# 2_cyber60-mx_matrix.net
KiCad netlist of a schematic drawn in Altium Designer
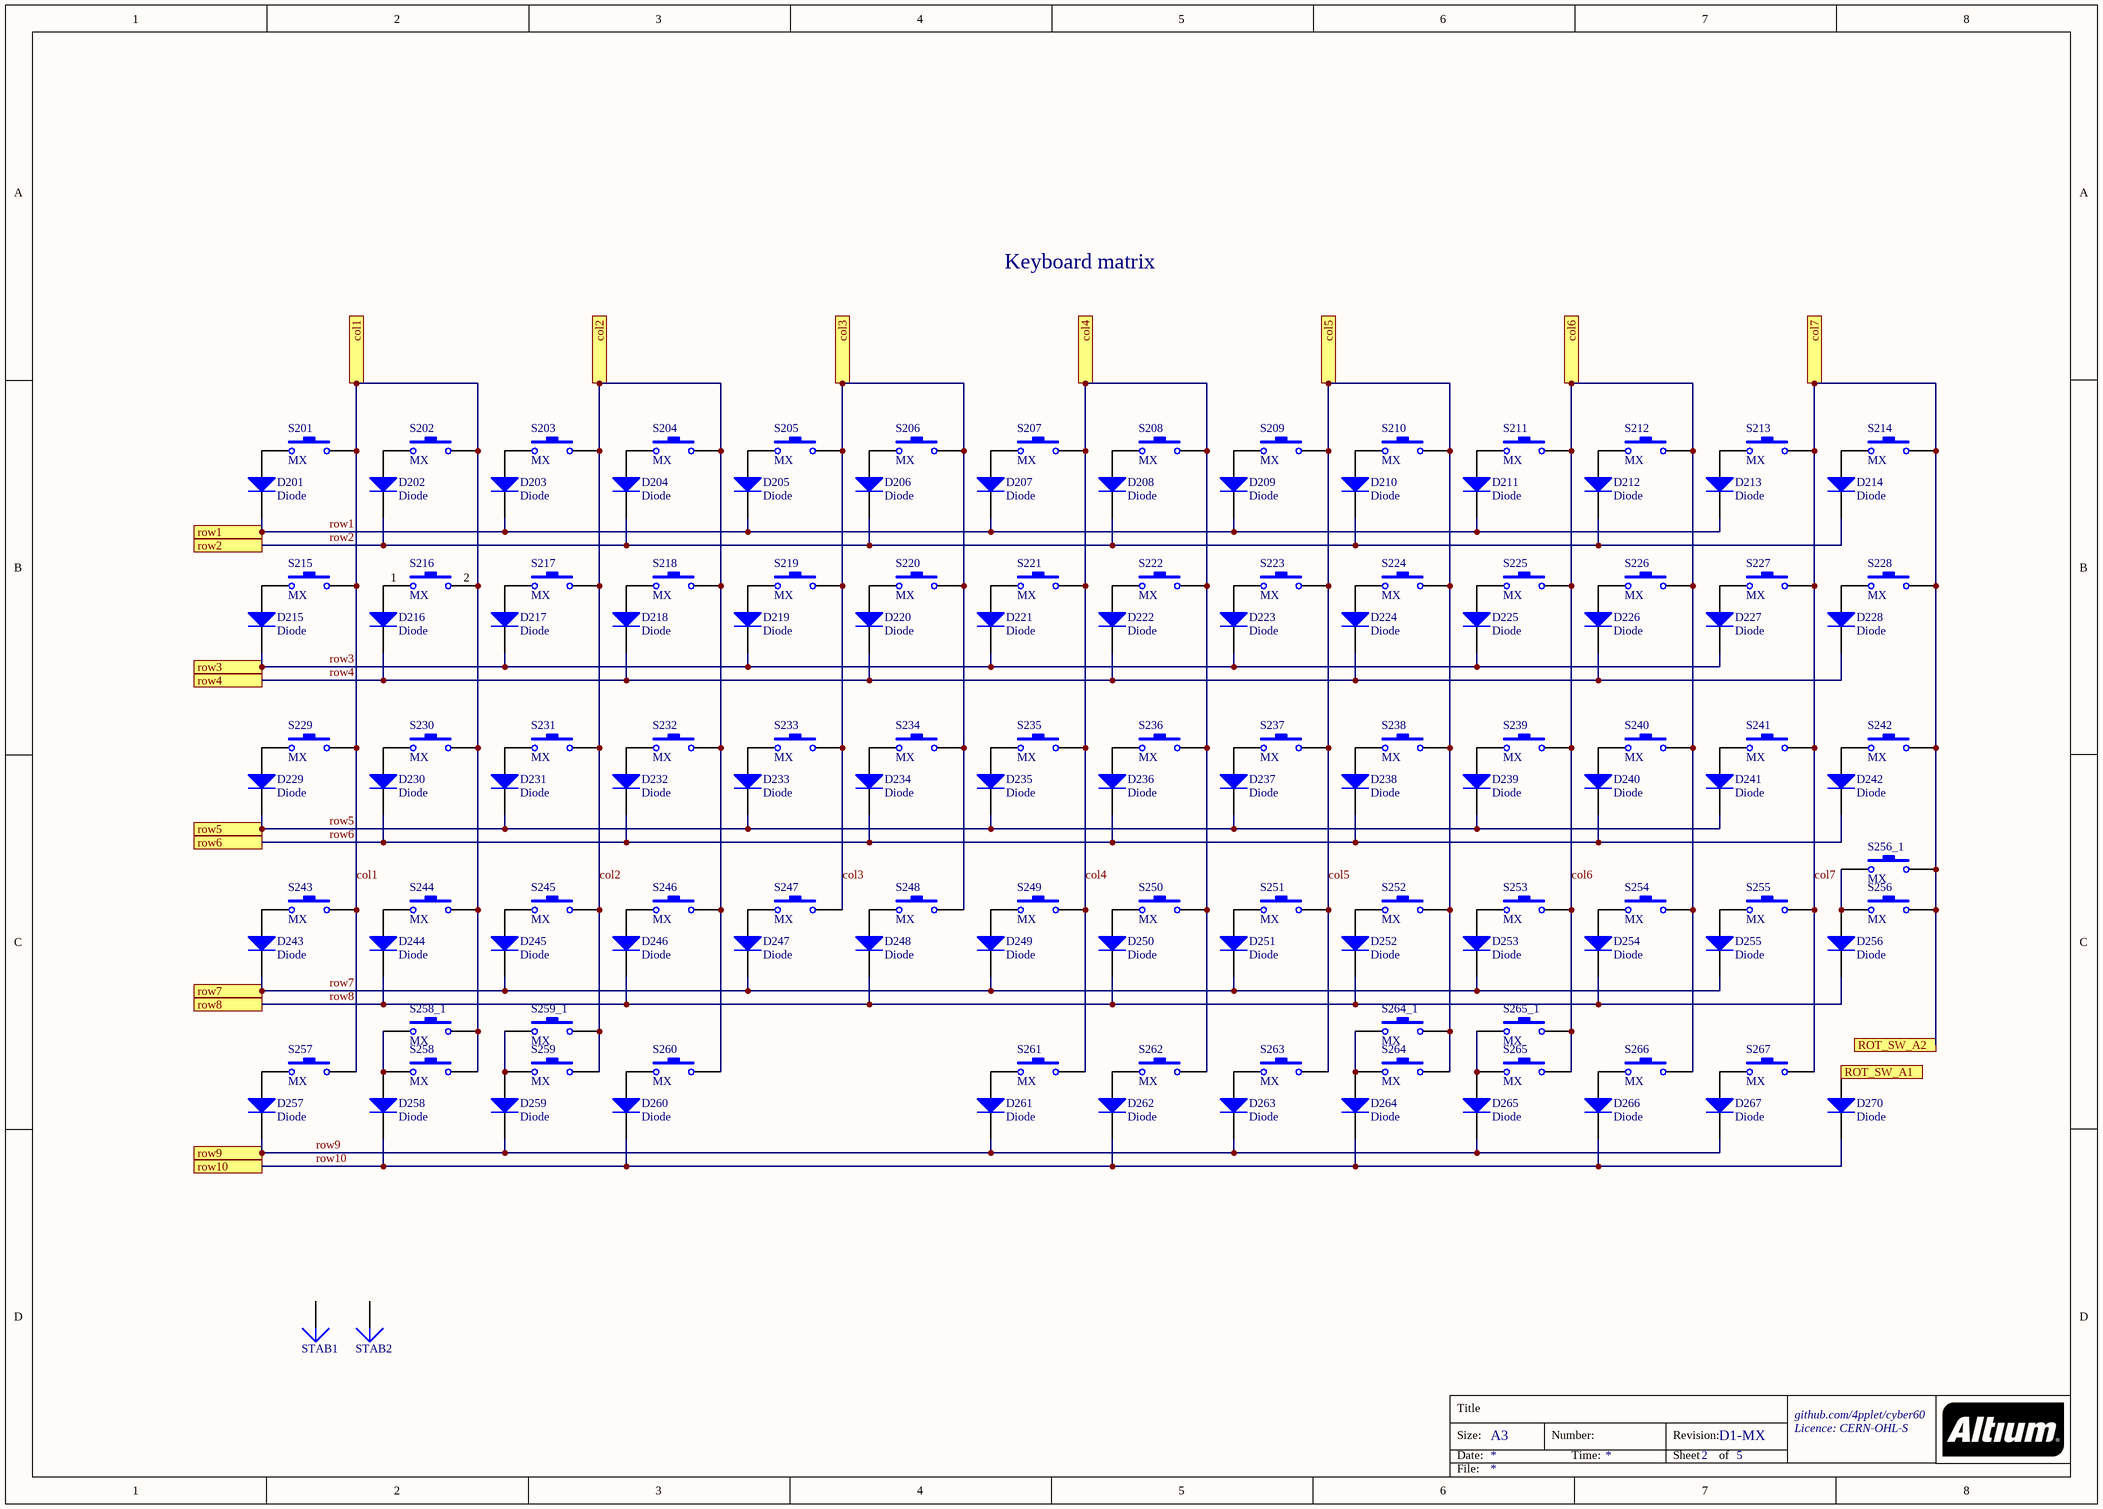
[diagram p0: 2_cyber60-mx_matrix.SchDoc]

(export (version "E")
  (design (tool "Eeschema 10.0.6"))
  (components
    (comp (ref "D201")
      (value "Diode")
      (footprint "SOD-123")
      (description "Default Diode")
      (fields (field (name "LCSC PART #") "C81598") (field (name "MRF.PART") "1N4148W"))
      (libsource (lib "Miscellaneous Devices") (part "Diode"))
    )
    (comp (ref "D202")
      (value "Diode")
      (footprint "SOD-123")
      (description "Default Diode")
      (fields (field (name "LCSC PART #") "C81598") (field (name "MRF.PART") "1N4148W"))
      (libsource (lib "Miscellaneous Devices") (part "Diode"))
    )
    (comp (ref "D203")
      (value "Diode")
      (footprint "SOD-123")
      (description "Default Diode")
      (fields (field (name "LCSC PART #") "C81598") (field (name "MRF.PART") "1N4148W"))
      (libsource (lib "Miscellaneous Devices") (part "Diode"))
    )
    (comp (ref "D204")
      (value "Diode")
      (footprint "SOD-123")
      (description "Default Diode")
      (fields (field (name "LCSC PART #") "C81598") (field (name "MRF.PART") "1N4148W"))
      (libsource (lib "Miscellaneous Devices") (part "Diode"))
    )
    (comp (ref "D205")
      (value "Diode")
      (footprint "SOD-123")
      (description "Default Diode")
      (fields (field (name "LCSC PART #") "C81598") (field (name "MRF.PART") "1N4148W"))
      (libsource (lib "Miscellaneous Devices") (part "Diode"))
    )
    (comp (ref "D206")
      (value "Diode")
      (footprint "SOD-123")
      (description "Default Diode")
      (fields (field (name "LCSC PART #") "C81598") (field (name "MRF.PART") "1N4148W"))
      (libsource (lib "Miscellaneous Devices") (part "Diode"))
    )
    (comp (ref "D207")
      (value "Diode")
      (footprint "SOD-123")
      (description "Default Diode")
      (fields (field (name "LCSC PART #") "C81598") (field (name "MRF.PART") "1N4148W"))
      (libsource (lib "Miscellaneous Devices") (part "Diode"))
    )
    (comp (ref "D208")
      (value "Diode")
      (footprint "SOD-123")
      (description "Default Diode")
      (fields (field (name "LCSC PART #") "C81598") (field (name "MRF.PART") "1N4148W"))
      (libsource (lib "Miscellaneous Devices") (part "Diode"))
    )
    (comp (ref "D209")
      (value "Diode")
      (footprint "SOD-123")
      (description "Default Diode")
      (fields (field (name "LCSC PART #") "C81598") (field (name "MRF.PART") "1N4148W"))
      (libsource (lib "Miscellaneous Devices") (part "Diode"))
    )
    (comp (ref "D210")
      (value "Diode")
      (footprint "SOD-123")
      (description "Default Diode")
      (fields (field (name "LCSC PART #") "C81598") (field (name "MRF.PART") "1N4148W"))
      (libsource (lib "Miscellaneous Devices") (part "Diode"))
    )
    (comp (ref "D211")
      (value "Diode")
      (footprint "SOD-123")
      (description "Default Diode")
      (fields (field (name "LCSC PART #") "C81598") (field (name "MRF.PART") "1N4148W"))
      (libsource (lib "Miscellaneous Devices") (part "Diode"))
    )
    (comp (ref "D212")
      (value "Diode")
      (footprint "SOD-123")
      (description "Default Diode")
      (fields (field (name "LCSC PART #") "C81598") (field (name "MRF.PART") "1N4148W"))
      (libsource (lib "Miscellaneous Devices") (part "Diode"))
    )
    (comp (ref "D213")
      (value "Diode")
      (footprint "SOD-123")
      (description "Default Diode")
      (fields (field (name "LCSC PART #") "C81598") (field (name "MRF.PART") "1N4148W"))
      (libsource (lib "Miscellaneous Devices") (part "Diode"))
    )
    (comp (ref "D214")
      (value "Diode")
      (footprint "SOD-123")
      (description "Default Diode")
      (fields (field (name "LCSC PART #") "C81598") (field (name "MRF.PART") "1N4148W"))
      (libsource (lib "Miscellaneous Devices") (part "Diode"))
    )
    (comp (ref "D215")
      (value "Diode")
      (footprint "SOD-123")
      (description "Default Diode")
      (fields (field (name "LCSC PART #") "C81598") (field (name "MRF.PART") "1N4148W"))
      (libsource (lib "Miscellaneous Devices") (part "Diode"))
    )
    (comp (ref "D216")
      (value "Diode")
      (footprint "SOD-123")
      (description "Default Diode")
      (fields (field (name "LCSC PART #") "C81598") (field (name "MRF.PART") "1N4148W"))
      (libsource (lib "Miscellaneous Devices") (part "Diode"))
    )
    (comp (ref "D217")
      (value "Diode")
      (footprint "SOD-123")
      (description "Default Diode")
      (fields (field (name "LCSC PART #") "C81598") (field (name "MRF.PART") "1N4148W"))
      (libsource (lib "Miscellaneous Devices") (part "Diode"))
    )
    (comp (ref "D218")
      (value "Diode")
      (footprint "SOD-123")
      (description "Default Diode")
      (fields (field (name "LCSC PART #") "C81598") (field (name "MRF.PART") "1N4148W"))
      (libsource (lib "Miscellaneous Devices") (part "Diode"))
    )
    (comp (ref "D219")
      (value "Diode")
      (footprint "SOD-123")
      (description "Default Diode")
      (fields (field (name "LCSC PART #") "C81598") (field (name "MRF.PART") "1N4148W"))
      (libsource (lib "Miscellaneous Devices") (part "Diode"))
    )
    (comp (ref "D220")
      (value "Diode")
      (footprint "SOD-123")
      (description "Default Diode")
      (fields (field (name "LCSC PART #") "C81598") (field (name "MRF.PART") "1N4148W"))
      (libsource (lib "Miscellaneous Devices") (part "Diode"))
    )
    (comp (ref "D221")
      (value "Diode")
      (footprint "SOD-123")
      (description "Default Diode")
      (fields (field (name "LCSC PART #") "C81598") (field (name "MRF.PART") "1N4148W"))
      (libsource (lib "Miscellaneous Devices") (part "Diode"))
    )
    (comp (ref "D222")
      (value "Diode")
      (footprint "SOD-123")
      (description "Default Diode")
      (fields (field (name "LCSC PART #") "C81598") (field (name "MRF.PART") "1N4148W"))
      (libsource (lib "Miscellaneous Devices") (part "Diode"))
    )
    (comp (ref "D223")
      (value "Diode")
      (footprint "SOD-123")
      (description "Default Diode")
      (fields (field (name "LCSC PART #") "C81598") (field (name "MRF.PART") "1N4148W"))
      (libsource (lib "Miscellaneous Devices") (part "Diode"))
    )
    (comp (ref "D224")
      (value "Diode")
      (footprint "SOD-123")
      (description "Default Diode")
      (fields (field (name "LCSC PART #") "C81598") (field (name "MRF.PART") "1N4148W"))
      (libsource (lib "Miscellaneous Devices") (part "Diode"))
    )
    (comp (ref "D225")
      (value "Diode")
      (footprint "SOD-123")
      (description "Default Diode")
      (fields (field (name "LCSC PART #") "C81598") (field (name "MRF.PART") "1N4148W"))
      (libsource (lib "Miscellaneous Devices") (part "Diode"))
    )
    (comp (ref "D226")
      (value "Diode")
      (footprint "SOD-123")
      (description "Default Diode")
      (fields (field (name "LCSC PART #") "C81598") (field (name "MRF.PART") "1N4148W"))
      (libsource (lib "Miscellaneous Devices") (part "Diode"))
    )
    (comp (ref "D227")
      (value "Diode")
      (footprint "SOD-123")
      (description "Default Diode")
      (fields (field (name "LCSC PART #") "C81598") (field (name "MRF.PART") "1N4148W"))
      (libsource (lib "Miscellaneous Devices") (part "Diode"))
    )
    (comp (ref "D228")
      (value "Diode")
      (footprint "SOD-123")
      (description "Default Diode")
      (fields (field (name "LCSC PART #") "C81598") (field (name "MRF.PART") "1N4148W"))
      (libsource (lib "Miscellaneous Devices") (part "Diode"))
    )
    (comp (ref "D229")
      (value "Diode")
      (footprint "SOD-123")
      (description "Default Diode")
      (fields (field (name "LCSC PART #") "C81598") (field (name "MRF.PART") "1N4148W"))
      (libsource (lib "Miscellaneous Devices") (part "Diode"))
    )
    (comp (ref "D230")
      (value "Diode")
      (footprint "SOD-123")
      (description "Default Diode")
      (fields (field (name "LCSC PART #") "C81598") (field (name "MRF.PART") "1N4148W"))
      (libsource (lib "Miscellaneous Devices") (part "Diode"))
    )
    (comp (ref "D231")
      (value "Diode")
      (footprint "SOD-123")
      (description "Default Diode")
      (fields (field (name "LCSC PART #") "C81598") (field (name "MRF.PART") "1N4148W"))
      (libsource (lib "Miscellaneous Devices") (part "Diode"))
    )
    (comp (ref "D232")
      (value "Diode")
      (footprint "SOD-123")
      (description "Default Diode")
      (fields (field (name "LCSC PART #") "C81598") (field (name "MRF.PART") "1N4148W"))
      (libsource (lib "Miscellaneous Devices") (part "Diode"))
    )
    (comp (ref "D233")
      (value "Diode")
      (footprint "SOD-123")
      (description "Default Diode")
      (fields (field (name "LCSC PART #") "C81598") (field (name "MRF.PART") "1N4148W"))
      (libsource (lib "Miscellaneous Devices") (part "Diode"))
    )
    (comp (ref "D234")
      (value "Diode")
      (footprint "SOD-123")
      (description "Default Diode")
      (fields (field (name "LCSC PART #") "C81598") (field (name "MRF.PART") "1N4148W"))
      (libsource (lib "Miscellaneous Devices") (part "Diode"))
    )
    (comp (ref "D235")
      (value "Diode")
      (footprint "SOD-123")
      (description "Default Diode")
      (fields (field (name "LCSC PART #") "C81598") (field (name "MRF.PART") "1N4148W"))
      (libsource (lib "Miscellaneous Devices") (part "Diode"))
    )
    (comp (ref "D236")
      (value "Diode")
      (footprint "SOD-123")
      (description "Default Diode")
      (fields (field (name "LCSC PART #") "C81598") (field (name "MRF.PART") "1N4148W"))
      (libsource (lib "Miscellaneous Devices") (part "Diode"))
    )
    (comp (ref "D237")
      (value "Diode")
      (footprint "SOD-123")
      (description "Default Diode")
      (fields (field (name "LCSC PART #") "C81598") (field (name "MRF.PART") "1N4148W"))
      (libsource (lib "Miscellaneous Devices") (part "Diode"))
    )
    (comp (ref "D238")
      (value "Diode")
      (footprint "SOD-123")
      (description "Default Diode")
      (fields (field (name "LCSC PART #") "C81598") (field (name "MRF.PART") "1N4148W"))
      (libsource (lib "Miscellaneous Devices") (part "Diode"))
    )
    (comp (ref "D239")
      (value "Diode")
      (footprint "SOD-123")
      (description "Default Diode")
      (fields (field (name "LCSC PART #") "C81598") (field (name "MRF.PART") "1N4148W"))
      (libsource (lib "Miscellaneous Devices") (part "Diode"))
    )
    (comp (ref "D240")
      (value "Diode")
      (footprint "SOD-123")
      (description "Default Diode")
      (fields (field (name "LCSC PART #") "C81598") (field (name "MRF.PART") "1N4148W"))
      (libsource (lib "Miscellaneous Devices") (part "Diode"))
    )
    (comp (ref "D241")
      (value "Diode")
      (footprint "SOD-123")
      (description "Default Diode")
      (fields (field (name "LCSC PART #") "C81598") (field (name "MRF.PART") "1N4148W"))
      (libsource (lib "Miscellaneous Devices") (part "Diode"))
    )
    (comp (ref "D242")
      (value "Diode")
      (footprint "SOD-123")
      (description "Default Diode")
      (fields (field (name "LCSC PART #") "C81598") (field (name "MRF.PART") "1N4148W"))
      (libsource (lib "Miscellaneous Devices") (part "Diode"))
    )
    (comp (ref "D243")
      (value "Diode")
      (footprint "SOD-123")
      (description "Default Diode")
      (fields (field (name "LCSC PART #") "C81598") (field (name "MRF.PART") "1N4148W"))
      (libsource (lib "Miscellaneous Devices") (part "Diode"))
    )
    (comp (ref "D244")
      (value "Diode")
      (footprint "SOD-123")
      (description "Default Diode")
      (fields (field (name "LCSC PART #") "C81598") (field (name "MRF.PART") "1N4148W"))
      (libsource (lib "Miscellaneous Devices") (part "Diode"))
    )
    (comp (ref "D245")
      (value "Diode")
      (footprint "SOD-123")
      (description "Default Diode")
      (fields (field (name "LCSC PART #") "C81598") (field (name "MRF.PART") "1N4148W"))
      (libsource (lib "Miscellaneous Devices") (part "Diode"))
    )
    (comp (ref "D246")
      (value "Diode")
      (footprint "SOD-123")
      (description "Default Diode")
      (fields (field (name "LCSC PART #") "C81598") (field (name "MRF.PART") "1N4148W"))
      (libsource (lib "Miscellaneous Devices") (part "Diode"))
    )
    (comp (ref "D247")
      (value "Diode")
      (footprint "SOD-123")
      (description "Default Diode")
      (fields (field (name "LCSC PART #") "C81598") (field (name "MRF.PART") "1N4148W"))
      (libsource (lib "Miscellaneous Devices") (part "Diode"))
    )
    (comp (ref "D248")
      (value "Diode")
      (footprint "SOD-123")
      (description "Default Diode")
      (fields (field (name "LCSC PART #") "C81598") (field (name "MRF.PART") "1N4148W"))
      (libsource (lib "Miscellaneous Devices") (part "Diode"))
    )
    (comp (ref "D249")
      (value "Diode")
      (footprint "SOD-123")
      (description "Default Diode")
      (fields (field (name "LCSC PART #") "C81598") (field (name "MRF.PART") "1N4148W"))
      (libsource (lib "Miscellaneous Devices") (part "Diode"))
    )
    (comp (ref "D250")
      (value "Diode")
      (footprint "SOD-123")
      (description "Default Diode")
      (fields (field (name "LCSC PART #") "C81598") (field (name "MRF.PART") "1N4148W"))
      (libsource (lib "Miscellaneous Devices") (part "Diode"))
    )
    (comp (ref "D251")
      (value "Diode")
      (footprint "SOD-123")
      (description "Default Diode")
      (fields (field (name "LCSC PART #") "C81598") (field (name "MRF.PART") "1N4148W"))
      (libsource (lib "Miscellaneous Devices") (part "Diode"))
    )
    (comp (ref "D252")
      (value "Diode")
      (footprint "SOD-123")
      (description "Default Diode")
      (fields (field (name "LCSC PART #") "C81598") (field (name "MRF.PART") "1N4148W"))
      (libsource (lib "Miscellaneous Devices") (part "Diode"))
    )
    (comp (ref "D253")
      (value "Diode")
      (footprint "SOD-123")
      (description "Default Diode")
      (fields (field (name "LCSC PART #") "C81598") (field (name "MRF.PART") "1N4148W"))
      (libsource (lib "Miscellaneous Devices") (part "Diode"))
    )
    (comp (ref "D254")
      (value "Diode")
      (footprint "SOD-123")
      (description "Default Diode")
      (fields (field (name "LCSC PART #") "C81598") (field (name "MRF.PART") "1N4148W"))
      (libsource (lib "Miscellaneous Devices") (part "Diode"))
    )
    (comp (ref "D255")
      (value "Diode")
      (footprint "SOD-123")
      (description "Default Diode")
      (fields (field (name "LCSC PART #") "C81598") (field (name "MRF.PART") "1N4148W"))
      (libsource (lib "Miscellaneous Devices") (part "Diode"))
    )
    (comp (ref "D256")
      (value "Diode")
      (footprint "SOD-123")
      (description "Default Diode")
      (fields (field (name "LCSC PART #") "C81598") (field (name "MRF.PART") "1N4148W"))
      (libsource (lib "Miscellaneous Devices") (part "Diode"))
    )
    (comp (ref "D257")
      (value "Diode")
      (footprint "SOD-123")
      (description "Default Diode")
      (fields (field (name "LCSC PART #") "C81598") (field (name "MRF.PART") "1N4148W"))
      (libsource (lib "Miscellaneous Devices") (part "Diode"))
    )
    (comp (ref "D258")
      (value "Diode")
      (footprint "SOD-123")
      (description "Default Diode")
      (fields (field (name "LCSC PART #") "C81598") (field (name "MRF.PART") "1N4148W"))
      (libsource (lib "Miscellaneous Devices") (part "Diode"))
    )
    (comp (ref "D259")
      (value "Diode")
      (footprint "SOD-123")
      (description "Default Diode")
      (fields (field (name "LCSC PART #") "C81598") (field (name "MRF.PART") "1N4148W"))
      (libsource (lib "Miscellaneous Devices") (part "Diode"))
    )
    (comp (ref "D260")
      (value "Diode")
      (footprint "SOD-123")
      (description "Default Diode")
      (fields (field (name "LCSC PART #") "C81598") (field (name "MRF.PART") "1N4148W"))
      (libsource (lib "Miscellaneous Devices") (part "Diode"))
    )
    (comp (ref "D261")
      (value "Diode")
      (footprint "SOD-123")
      (description "Default Diode")
      (fields (field (name "LCSC PART #") "C81598") (field (name "MRF.PART") "1N4148W"))
      (libsource (lib "Miscellaneous Devices") (part "Diode"))
    )
    (comp (ref "D262")
      (value "Diode")
      (footprint "SOD-123")
      (description "Default Diode")
      (fields (field (name "LCSC PART #") "C81598") (field (name "MRF.PART") "1N4148W"))
      (libsource (lib "Miscellaneous Devices") (part "Diode"))
    )
    (comp (ref "D263")
      (value "Diode")
      (footprint "SOD-123")
      (description "Default Diode")
      (fields (field (name "LCSC PART #") "C81598") (field (name "MRF.PART") "1N4148W"))
      (libsource (lib "Miscellaneous Devices") (part "Diode"))
    )
    (comp (ref "D264")
      (value "Diode")
      (footprint "SOD-123")
      (description "Default Diode")
      (fields (field (name "LCSC PART #") "C81598") (field (name "MRF.PART") "1N4148W"))
      (libsource (lib "Miscellaneous Devices") (part "Diode"))
    )
    (comp (ref "D265")
      (value "Diode")
      (footprint "SOD-123")
      (description "Default Diode")
      (fields (field (name "LCSC PART #") "C81598") (field (name "MRF.PART") "1N4148W"))
      (libsource (lib "Miscellaneous Devices") (part "Diode"))
    )
    (comp (ref "D266")
      (value "Diode")
      (footprint "SOD-123")
      (description "Default Diode")
      (fields (field (name "LCSC PART #") "C81598") (field (name "MRF.PART") "1N4148W"))
      (libsource (lib "Miscellaneous Devices") (part "Diode"))
    )
    (comp (ref "D267")
      (value "Diode")
      (footprint "SOD-123")
      (description "Default Diode")
      (fields (field (name "LCSC PART #") "C81598") (field (name "MRF.PART") "1N4148W"))
      (libsource (lib "Miscellaneous Devices") (part "Diode"))
    )
    (comp (ref "D270")
      (value "Diode")
      (footprint "SOD-123")
      (description "Default Diode")
      (fields (field (name "LCSC PART #") "C81598") (field (name "MRF.PART") "1N4148W"))
      (libsource (lib "Miscellaneous Devices") (part "Diode"))
    )
    (comp (ref "S201")
      (value "MX")
      (footprint "MX-switch - switched pol")
      (description "Switch")
      (libsource (lib "Miscellaneous Devices") (part "SW-PB"))
    )
    (comp (ref "S202")
      (value "MX")
      (footprint "MX-switch - switched pol - connector")
      (description "Switch")
      (libsource (lib "Miscellaneous Devices") (part "SW-PB"))
    )
    (comp (ref "S203")
      (value "MX")
      (footprint "MX-switch - switched pol")
      (description "Switch")
      (libsource (lib "Miscellaneous Devices") (part "SW-PB"))
    )
    (comp (ref "S204")
      (value "MX")
      (footprint "MX-switch")
      (description "Switch")
      (libsource (lib "Miscellaneous Devices") (part "SW-PB"))
    )
    (comp (ref "S205")
      (value "MX")
      (footprint "MX-switch - switched pol")
      (description "Switch")
      (libsource (lib "Miscellaneous Devices") (part "SW-PB"))
    )
    (comp (ref "S206")
      (value "MX")
      (footprint "MX-switch - switched pol")
      (description "Switch")
      (libsource (lib "Miscellaneous Devices") (part "SW-PB"))
    )
    (comp (ref "S207")
      (value "MX")
      (footprint "MX-switch - switched pol")
      (description "Switch")
      (libsource (lib "Miscellaneous Devices") (part "SW-PB"))
    )
    (comp (ref "S208")
      (value "MX")
      (footprint "MX-switch - switched pol")
      (description "Switch")
      (libsource (lib "Miscellaneous Devices") (part "SW-PB"))
    )
    (comp (ref "S209")
      (value "MX")
      (footprint "MX-switch - switched pol")
      (description "Switch")
      (libsource (lib "Miscellaneous Devices") (part "SW-PB"))
    )
    (comp (ref "S210")
      (value "MX")
      (footprint "MX-switch - switched pol")
      (description "Switch")
      (libsource (lib "Miscellaneous Devices") (part "SW-PB"))
    )
    (comp (ref "S211")
      (value "MX")
      (footprint "MX-switch - switched pol")
      (description "Switch")
      (libsource (lib "Miscellaneous Devices") (part "SW-PB"))
    )
    (comp (ref "S212")
      (value "MX")
      (footprint "MX-switch - switched pol")
      (description "Switch")
      (libsource (lib "Miscellaneous Devices") (part "SW-PB"))
    )
    (comp (ref "S213")
      (value "MX")
      (footprint "MX-switch - switched pol")
      (description "Switch")
      (libsource (lib "Miscellaneous Devices") (part "SW-PB"))
    )
    (comp (ref "S214")
      (value "MX")
      (footprint "MX-switch - switched pol")
      (description "Switch")
      (libsource (lib "Miscellaneous Devices") (part "SW-PB"))
    )
    (comp (ref "S215")
      (value "MX")
      (footprint "MX-switch - 1.5U - switched pol")
      (description "TAB")
      (libsource (lib "Miscellaneous Devices") (part "SW-PB"))
    )
    (comp (ref "S216")
      (value "MX")
      (footprint "MX-switch - switched pol")
      (description "Switch")
      (libsource (lib "") (part "SW-PB_1"))
    )
    (comp (ref "S217")
      (value "MX")
      (footprint "MX-switch - switched pol")
      (description "Switch")
      (libsource (lib "Miscellaneous Devices") (part "SW-PB"))
    )
    (comp (ref "S218")
      (value "MX")
      (footprint "MX-switch - switched pol")
      (description "Switch")
      (libsource (lib "Miscellaneous Devices") (part "SW-PB"))
    )
    (comp (ref "S219")
      (value "MX")
      (footprint "MX-switch - switched pol")
      (description "Switch")
      (libsource (lib "Miscellaneous Devices") (part "SW-PB"))
    )
    (comp (ref "S220")
      (value "MX")
      (footprint "MX-switch")
      (description "Switch")
      (libsource (lib "Miscellaneous Devices") (part "SW-PB"))
    )
    (comp (ref "S221")
      (value "MX")
      (footprint "MX-switch - switched pol")
      (description "Switch")
      (libsource (lib "Miscellaneous Devices") (part "SW-PB"))
    )
    (comp (ref "S222")
      (value "MX")
      (footprint "MX-switch - switched pol")
      (description "Switch")
      (libsource (lib "Miscellaneous Devices") (part "SW-PB"))
    )
    (comp (ref "S223")
      (value "MX")
      (footprint "MX-switch - switched pol")
      (description "Switch")
      (libsource (lib "Miscellaneous Devices") (part "SW-PB"))
    )
    (comp (ref "S224")
      (value "MX")
      (footprint "MX-switch - switched pol")
      (description "Switch")
      (libsource (lib "Miscellaneous Devices") (part "SW-PB"))
    )
    (comp (ref "S225")
      (value "MX")
      (footprint "MX-switch - switched pol")
      (description "Switch")
      (libsource (lib "Miscellaneous Devices") (part "SW-PB"))
    )
    (comp (ref "S226")
      (value "MX")
      (footprint "MX-switch")
      (description "Switch")
      (libsource (lib "Miscellaneous Devices") (part "SW-PB"))
    )
    (comp (ref "S227")
      (value "MX")
      (footprint "MX-switch")
      (description "Switch")
      (libsource (lib "Miscellaneous Devices") (part "SW-PB"))
    )
    (comp (ref "S228")
      (value "MX")
      (footprint "MX-switch - backspace")
      (description "Switch")
      (libsource (lib "Miscellaneous Devices") (part "SW-PB"))
    )
    (comp (ref "S229")
      (value "MX")
      (footprint "MX-switch - CAPS")
      (description "Switch")
      (libsource (lib "Miscellaneous Devices") (part "SW-PB"))
    )
    (comp (ref "S230")
      (value "MX")
      (footprint "MX-switch - switched pol")
      (description "Switch")
      (libsource (lib "Miscellaneous Devices") (part "SW-PB"))
    )
    (comp (ref "S231")
      (value "MX")
      (footprint "MX-switch - switched pol")
      (description "Switch")
      (libsource (lib "Miscellaneous Devices") (part "SW-PB"))
    )
    (comp (ref "S232")
      (value "MX")
      (footprint "MX-switch - switched pol")
      (description "Switch")
      (libsource (lib "Miscellaneous Devices") (part "SW-PB"))
    )
    (comp (ref "S233")
      (value "MX")
      (footprint "MX-switch - switched pol")
      (description "Switch")
      (libsource (lib "Miscellaneous Devices") (part "SW-PB"))
    )
    (comp (ref "S234")
      (value "MX")
      (footprint "MX-switch")
      (description "Switch")
      (libsource (lib "Miscellaneous Devices") (part "SW-PB"))
    )
    (comp (ref "S235")
      (value "MX")
      (footprint "MX-switch - switched pol")
      (description "Switch")
      (libsource (lib "Miscellaneous Devices") (part "SW-PB"))
    )
    (comp (ref "S236")
      (value "MX")
      (footprint "MX-switch - switched pol")
      (description "Switch")
      (libsource (lib "Miscellaneous Devices") (part "SW-PB"))
    )
    (comp (ref "S237")
      (value "MX")
      (footprint "MX-switch - switched pol")
      (description "Switch")
      (libsource (lib "Miscellaneous Devices") (part "SW-PB"))
    )
    (comp (ref "S238")
      (value "MX")
      (footprint "MX-switch - switched pol")
      (description "Switch")
      (libsource (lib "Miscellaneous Devices") (part "SW-PB"))
    )
    (comp (ref "S239")
      (value "MX")
      (footprint "MX-switch")
      (description "Switch")
      (libsource (lib "Miscellaneous Devices") (part "SW-PB"))
    )
    (comp (ref "S240")
      (value "MX")
      (footprint "MX-switch - switched pol")
      (description "Switch")
      (libsource (lib "Miscellaneous Devices") (part "SW-PB"))
    )
    (comp (ref "S241")
      (value "MX")
      (footprint "MX-switch")
      (description "Switch")
      (libsource (lib "Miscellaneous Devices") (part "SW-PB"))
    )
    (comp (ref "S242")
      (value "MX")
      (footprint "MX-switch - 1.5U")
      (description "Switch")
      (libsource (lib "Miscellaneous Devices") (part "SW-PB"))
    )
    (comp (ref "S243")
      (value "MX")
      (footprint "MX-switch - Left shift")
      (description "Switch")
      (libsource (lib "Miscellaneous Devices") (part "SW-PB"))
    )
    (comp (ref "S244")
      (value "MX")
      (footprint "MX-switch - switched pol")
      (description "Switch")
      (libsource (lib "Miscellaneous Devices") (part "SW-PB"))
    )
    (comp (ref "S245")
      (value "MX")
      (footprint "MX-switch - switched pol")
      (description "Switch")
      (libsource (lib "Miscellaneous Devices") (part "SW-PB"))
    )
    (comp (ref "S246")
      (value "MX")
      (footprint "MX-switch - switched pol")
      (description "Switch")
      (libsource (lib "Miscellaneous Devices") (part "SW-PB"))
    )
    (comp (ref "S247")
      (value "MX")
      (footprint "MX-switch - switched pol")
      (description "Switch")
      (libsource (lib "Miscellaneous Devices") (part "SW-PB"))
    )
    (comp (ref "S248")
      (value "MX")
      (footprint "MX-switch")
      (description "Switch")
      (libsource (lib "Miscellaneous Devices") (part "SW-PB"))
    )
    (comp (ref "S249")
      (value "MX")
      (footprint "MX-switch - switched pol")
      (description "Switch")
      (libsource (lib "Miscellaneous Devices") (part "SW-PB"))
    )
    (comp (ref "S250")
      (value "MX")
      (footprint "MX-switch")
      (description "Switch")
      (libsource (lib "Miscellaneous Devices") (part "SW-PB"))
    )
    (comp (ref "S251")
      (value "MX")
      (footprint "MX-switch - switched pol")
      (description "Switch")
      (libsource (lib "Miscellaneous Devices") (part "SW-PB"))
    )
    (comp (ref "S252")
      (value "MX")
      (footprint "MX-switch - switched pol")
      (description "Switch")
      (libsource (lib "Miscellaneous Devices") (part "SW-PB"))
    )
    (comp (ref "S253")
      (value "MX")
      (footprint "MX-switch - switched pol")
      (description "Switch")
      (libsource (lib "Miscellaneous Devices") (part "SW-PB"))
    )
    (comp (ref "S254")
      (value "MX")
      (footprint "MX-switch - switched pol")
      (description "Switch")
      (libsource (lib "Miscellaneous Devices") (part "SW-PB"))
    )
    (comp (ref "S255")
      (value "MX")
      (footprint "MX-switch")
      (description "Switch")
      (libsource (lib "Miscellaneous Devices") (part "SW-PB"))
    )
    (comp (ref "S256")
      (value "MX")
      (footprint "MX-switch - switched pol")
      (description "Switch")
      (libsource (lib "Miscellaneous Devices") (part "SW-PB"))
    )
    (comp (ref "S256_1")
      (value "MX")
      (footprint "MX-switch")
      (description "Switch")
      (libsource (lib "Miscellaneous Devices") (part "SW-PB"))
    )
    (comp (ref "S257")
      (value "MX")
      (footprint "MX-switch - 1.5u MOD-L")
      (description "Switch")
      (libsource (lib "Miscellaneous Devices") (part "SW-PB"))
    )
    (comp (ref "S258")
      (value "MX")
      (footprint "MX-switch - 1u MOD-L")
      (description "Switch")
      (libsource (lib "Miscellaneous Devices") (part "SW-PB"))
    )
    (comp (ref "S258_1")
      (value "MX")
      (footprint "MX-switch")
      (description "Switch")
      (libsource (lib "Miscellaneous Devices") (part "SW-PB"))
    )
    (comp (ref "S259")
      (value "MX")
      (footprint "MX-switch - 1.5u MOD-L")
      (description "Switch")
      (libsource (lib "Miscellaneous Devices") (part "SW-PB"))
    )
    (comp (ref "S259_1")
      (value "MX")
      (footprint "MX-switch - switched pol")
      (description "Switch")
      (libsource (lib "Miscellaneous Devices") (part "SW-PB"))
    )
    (comp (ref "S260")
      (value "MX")
      (footprint "MX-switch - 2.75U - rotated stab")
      (description "Switch")
      (libsource (lib "Miscellaneous Devices") (part "SW-PB"))
    )
    (comp (ref "S261")
      (value "MX")
      (footprint "MX-switch - Space_V2")
      (description "Switch")
      (libsource (lib "Miscellaneous Devices") (part "SW-PB"))
    )
    (comp (ref "S262")
      (value "MX")
      (footprint "MX-switch - 2.75U - rotated stab")
      (description "Switch")
      (libsource (lib "Miscellaneous Devices") (part "SW-PB"))
    )
    (comp (ref "S263")
      (value "MX")
      (footprint "MX-switch - switched pol")
      (description "Switch")
      (libsource (lib "Miscellaneous Devices") (part "SW-PB"))
    )
    (comp (ref "S264")
      (value "MX")
      (footprint "MX-switch - 1.5u MOD-R")
      (description "Switch")
      (libsource (lib "Miscellaneous Devices") (part "SW-PB"))
    )
    (comp (ref "S264_1")
      (value "MX")
      (footprint "MX-switch")
      (description "Switch")
      (libsource (lib "Miscellaneous Devices") (part "SW-PB"))
    )
    (comp (ref "S265")
      (value "MX")
      (footprint "MX-switch - 1u MOD-R")
      (description "Switch")
      (libsource (lib "Miscellaneous Devices") (part "SW-PB"))
    )
    (comp (ref "S265_1")
      (value "MX")
      (footprint "MX-switch")
      (description "Switch")
      (libsource (lib "Miscellaneous Devices") (part "SW-PB"))
    )
    (comp (ref "S266")
      (value "MX")
      (footprint "MX-switch - 1.5u MOD-R")
      (description "Switch")
      (libsource (lib "Miscellaneous Devices") (part "SW-PB"))
    )
    (comp (ref "S267")
      (value "MX")
      (footprint "MX-switch - right shift")
      (description "Switch")
      (libsource (lib "Miscellaneous Devices") (part "SW-PB"))
    )
    (comp (ref "STAB1")
      (value "Plug")
      (footprint "Stab 2u")
      (libsource (lib "Miscellaneous Connectors") (part "Plug"))
    )
    (comp (ref "STAB2")
      (value "Plug")
      (footprint "Stab 2u")
      (libsource (lib "Miscellaneous Connectors") (part "Plug"))
    )
  )
  (nets
    (net (code "1") (name "/ROT_SW_A1") (class "Default")
      (node (ref "D270") (pin "1") (pinfunction "A_1") (pintype "passive"))
    )
    (net (code "2") (name "/col1") (class "Default")
      (node (ref "S201") (pin "2") (pinfunction "2_2") (pintype "passive"))
      (node (ref "S202") (pin "2") (pinfunction "2_2") (pintype "passive"))
      (node (ref "S215") (pin "2") (pinfunction "2_2") (pintype "passive"))
      (node (ref "S216") (pin "2") (pinfunction "2_2") (pintype "passive"))
      (node (ref "S229") (pin "2") (pinfunction "2_2") (pintype "passive"))
      (node (ref "S230") (pin "2") (pinfunction "2_2") (pintype "passive"))
      (node (ref "S243") (pin "2") (pinfunction "2_2") (pintype "passive"))
      (node (ref "S244") (pin "2") (pinfunction "2_2") (pintype "passive"))
      (node (ref "S257") (pin "2") (pinfunction "2_2") (pintype "passive"))
      (node (ref "S258") (pin "2") (pinfunction "2_2") (pintype "passive"))
      (node (ref "S258_1") (pin "2") (pinfunction "2_2") (pintype "passive"))
    )
    (net (code "3") (name "/col2") (class "Default")
      (node (ref "S203") (pin "2") (pinfunction "2_2") (pintype "passive"))
      (node (ref "S204") (pin "2") (pinfunction "2_2") (pintype "passive"))
      (node (ref "S217") (pin "2") (pinfunction "2_2") (pintype "passive"))
      (node (ref "S218") (pin "2") (pinfunction "2_2") (pintype "passive"))
      (node (ref "S231") (pin "2") (pinfunction "2_2") (pintype "passive"))
      (node (ref "S232") (pin "2") (pinfunction "2_2") (pintype "passive"))
      (node (ref "S245") (pin "2") (pinfunction "2_2") (pintype "passive"))
      (node (ref "S246") (pin "2") (pinfunction "2_2") (pintype "passive"))
      (node (ref "S259") (pin "2") (pinfunction "2_2") (pintype "passive"))
      (node (ref "S259_1") (pin "2") (pinfunction "2_2") (pintype "passive"))
      (node (ref "S260") (pin "2") (pinfunction "2_2") (pintype "passive"))
    )
    (net (code "4") (name "/col3") (class "Default")
      (node (ref "S205") (pin "2") (pinfunction "2_2") (pintype "passive"))
      (node (ref "S206") (pin "2") (pinfunction "2_2") (pintype "passive"))
      (node (ref "S219") (pin "2") (pinfunction "2_2") (pintype "passive"))
      (node (ref "S220") (pin "2") (pinfunction "2_2") (pintype "passive"))
      (node (ref "S233") (pin "2") (pinfunction "2_2") (pintype "passive"))
      (node (ref "S234") (pin "2") (pinfunction "2_2") (pintype "passive"))
      (node (ref "S247") (pin "2") (pinfunction "2_2") (pintype "passive"))
      (node (ref "S248") (pin "2") (pinfunction "2_2") (pintype "passive"))
    )
    (net (code "5") (name "/col4") (class "Default")
      (node (ref "S207") (pin "2") (pinfunction "2_2") (pintype "passive"))
      (node (ref "S208") (pin "2") (pinfunction "2_2") (pintype "passive"))
      (node (ref "S221") (pin "2") (pinfunction "2_2") (pintype "passive"))
      (node (ref "S222") (pin "2") (pinfunction "2_2") (pintype "passive"))
      (node (ref "S235") (pin "2") (pinfunction "2_2") (pintype "passive"))
      (node (ref "S236") (pin "2") (pinfunction "2_2") (pintype "passive"))
      (node (ref "S249") (pin "2") (pinfunction "2_2") (pintype "passive"))
      (node (ref "S250") (pin "2") (pinfunction "2_2") (pintype "passive"))
      (node (ref "S261") (pin "1") (pinfunction "1_1") (pintype "passive"))
      (node (ref "S262") (pin "2") (pinfunction "2_2") (pintype "passive"))
    )
    (net (code "6") (name "/col5") (class "Default")
      (node (ref "S209") (pin "2") (pinfunction "2_2") (pintype "passive"))
      (node (ref "S210") (pin "2") (pinfunction "2_2") (pintype "passive"))
      (node (ref "S223") (pin "2") (pinfunction "2_2") (pintype "passive"))
      (node (ref "S224") (pin "2") (pinfunction "2_2") (pintype "passive"))
      (node (ref "S237") (pin "2") (pinfunction "2_2") (pintype "passive"))
      (node (ref "S238") (pin "2") (pinfunction "2_2") (pintype "passive"))
      (node (ref "S251") (pin "2") (pinfunction "2_2") (pintype "passive"))
      (node (ref "S252") (pin "2") (pinfunction "2_2") (pintype "passive"))
      (node (ref "S263") (pin "2") (pinfunction "2_2") (pintype "passive"))
      (node (ref "S264") (pin "1") (pinfunction "1_1") (pintype "passive"))
      (node (ref "S264_1") (pin "2") (pinfunction "2_2") (pintype "passive"))
    )
    (net (code "7") (name "/col6") (class "Default")
      (node (ref "S211") (pin "2") (pinfunction "2_2") (pintype "passive"))
      (node (ref "S212") (pin "2") (pinfunction "2_2") (pintype "passive"))
      (node (ref "S225") (pin "2") (pinfunction "2_2") (pintype "passive"))
      (node (ref "S226") (pin "2") (pinfunction "2_2") (pintype "passive"))
      (node (ref "S239") (pin "2") (pinfunction "2_2") (pintype "passive"))
      (node (ref "S240") (pin "2") (pinfunction "2_2") (pintype "passive"))
      (node (ref "S253") (pin "2") (pinfunction "2_2") (pintype "passive"))
      (node (ref "S254") (pin "2") (pinfunction "2_2") (pintype "passive"))
      (node (ref "S265") (pin "2") (pinfunction "2_2") (pintype "passive"))
      (node (ref "S265_1") (pin "2") (pinfunction "2_2") (pintype "passive"))
      (node (ref "S266") (pin "2") (pinfunction "2_2") (pintype "passive"))
    )
    (net (code "8") (name "/col7") (class "Default")
      (node (ref "S213") (pin "2") (pinfunction "2_2") (pintype "passive"))
      (node (ref "S214") (pin "2") (pinfunction "2_2") (pintype "passive"))
      (node (ref "S227") (pin "2") (pinfunction "2_2") (pintype "passive"))
      (node (ref "S228") (pin "1") (pinfunction "1_1") (pintype "passive"))
      (node (ref "S241") (pin "2") (pinfunction "2_2") (pintype "passive"))
      (node (ref "S242") (pin "2") (pinfunction "2_2") (pintype "passive"))
      (node (ref "S255") (pin "2") (pinfunction "2_2") (pintype "passive"))
      (node (ref "S256") (pin "2") (pinfunction "2_2") (pintype "passive"))
      (node (ref "S256_1") (pin "2") (pinfunction "2_2") (pintype "passive"))
      (node (ref "S267") (pin "2") (pinfunction "2_2") (pintype "passive"))
    )
    (net (code "9") (name "/row1") (class "Default")
      (node (ref "D201") (pin "2") (pinfunction "K_2") (pintype "passive"))
      (node (ref "D203") (pin "2") (pinfunction "K_2") (pintype "passive"))
      (node (ref "D205") (pin "2") (pinfunction "K_2") (pintype "passive"))
      (node (ref "D207") (pin "2") (pinfunction "K_2") (pintype "passive"))
      (node (ref "D209") (pin "2") (pinfunction "K_2") (pintype "passive"))
      (node (ref "D211") (pin "2") (pinfunction "K_2") (pintype "passive"))
      (node (ref "D213") (pin "2") (pinfunction "K_2") (pintype "passive"))
    )
    (net (code "10") (name "/row2") (class "Default")
      (node (ref "D202") (pin "2") (pinfunction "K_2") (pintype "passive"))
      (node (ref "D204") (pin "2") (pinfunction "K_2") (pintype "passive"))
      (node (ref "D206") (pin "2") (pinfunction "K_2") (pintype "passive"))
      (node (ref "D208") (pin "2") (pinfunction "K_2") (pintype "passive"))
      (node (ref "D210") (pin "2") (pinfunction "K_2") (pintype "passive"))
      (node (ref "D212") (pin "2") (pinfunction "K_2") (pintype "passive"))
      (node (ref "D214") (pin "2") (pinfunction "K_2") (pintype "passive"))
    )
    (net (code "11") (name "/row3") (class "Default")
      (node (ref "D215") (pin "2") (pinfunction "K_2") (pintype "passive"))
      (node (ref "D217") (pin "2") (pinfunction "K_2") (pintype "passive"))
      (node (ref "D219") (pin "2") (pinfunction "K_2") (pintype "passive"))
      (node (ref "D221") (pin "2") (pinfunction "K_2") (pintype "passive"))
      (node (ref "D223") (pin "2") (pinfunction "K_2") (pintype "passive"))
      (node (ref "D225") (pin "2") (pinfunction "K_2") (pintype "passive"))
      (node (ref "D227") (pin "2") (pinfunction "K_2") (pintype "passive"))
    )
    (net (code "12") (name "/row4") (class "Default")
      (node (ref "D216") (pin "2") (pinfunction "K_2") (pintype "passive"))
      (node (ref "D218") (pin "2") (pinfunction "K_2") (pintype "passive"))
      (node (ref "D220") (pin "2") (pinfunction "K_2") (pintype "passive"))
      (node (ref "D222") (pin "2") (pinfunction "K_2") (pintype "passive"))
      (node (ref "D224") (pin "2") (pinfunction "K_2") (pintype "passive"))
      (node (ref "D226") (pin "2") (pinfunction "K_2") (pintype "passive"))
      (node (ref "D228") (pin "2") (pinfunction "K_2") (pintype "passive"))
    )
    (net (code "13") (name "/row5") (class "Default")
      (node (ref "D229") (pin "2") (pinfunction "K_2") (pintype "passive"))
      (node (ref "D231") (pin "2") (pinfunction "K_2") (pintype "passive"))
      (node (ref "D233") (pin "2") (pinfunction "K_2") (pintype "passive"))
      (node (ref "D235") (pin "2") (pinfunction "K_2") (pintype "passive"))
      (node (ref "D237") (pin "2") (pinfunction "K_2") (pintype "passive"))
      (node (ref "D239") (pin "2") (pinfunction "K_2") (pintype "passive"))
      (node (ref "D241") (pin "2") (pinfunction "K_2") (pintype "passive"))
    )
    (net (code "14") (name "/row6") (class "Default")
      (node (ref "D230") (pin "2") (pinfunction "K_2") (pintype "passive"))
      (node (ref "D232") (pin "2") (pinfunction "K_2") (pintype "passive"))
      (node (ref "D234") (pin "2") (pinfunction "K_2") (pintype "passive"))
      (node (ref "D236") (pin "2") (pinfunction "K_2") (pintype "passive"))
      (node (ref "D238") (pin "2") (pinfunction "K_2") (pintype "passive"))
      (node (ref "D240") (pin "2") (pinfunction "K_2") (pintype "passive"))
      (node (ref "D242") (pin "2") (pinfunction "K_2") (pintype "passive"))
    )
    (net (code "15") (name "/row7") (class "Default")
      (node (ref "D243") (pin "2") (pinfunction "K_2") (pintype "passive"))
      (node (ref "D245") (pin "2") (pinfunction "K_2") (pintype "passive"))
      (node (ref "D247") (pin "2") (pinfunction "K_2") (pintype "passive"))
      (node (ref "D249") (pin "2") (pinfunction "K_2") (pintype "passive"))
      (node (ref "D251") (pin "2") (pinfunction "K_2") (pintype "passive"))
      (node (ref "D253") (pin "2") (pinfunction "K_2") (pintype "passive"))
      (node (ref "D255") (pin "2") (pinfunction "K_2") (pintype "passive"))
    )
    (net (code "16") (name "/row8") (class "Default")
      (node (ref "D244") (pin "2") (pinfunction "K_2") (pintype "passive"))
      (node (ref "D246") (pin "2") (pinfunction "K_2") (pintype "passive"))
      (node (ref "D248") (pin "2") (pinfunction "K_2") (pintype "passive"))
      (node (ref "D250") (pin "2") (pinfunction "K_2") (pintype "passive"))
      (node (ref "D252") (pin "2") (pinfunction "K_2") (pintype "passive"))
      (node (ref "D254") (pin "2") (pinfunction "K_2") (pintype "passive"))
      (node (ref "D256") (pin "2") (pinfunction "K_2") (pintype "passive"))
    )
    (net (code "17") (name "/row9") (class "Default")
      (node (ref "D257") (pin "2") (pinfunction "K_2") (pintype "passive"))
      (node (ref "D259") (pin "2") (pinfunction "K_2") (pintype "passive"))
      (node (ref "D261") (pin "2") (pinfunction "K_2") (pintype "passive"))
      (node (ref "D263") (pin "2") (pinfunction "K_2") (pintype "passive"))
      (node (ref "D265") (pin "2") (pinfunction "K_2") (pintype "passive"))
      (node (ref "D267") (pin "2") (pinfunction "K_2") (pintype "passive"))
    )
    (net (code "18") (name "/row10") (class "Default")
      (node (ref "D258") (pin "2") (pinfunction "K_2") (pintype "passive"))
      (node (ref "D260") (pin "2") (pinfunction "K_2") (pintype "passive"))
      (node (ref "D262") (pin "2") (pinfunction "K_2") (pintype "passive"))
      (node (ref "D264") (pin "2") (pinfunction "K_2") (pintype "passive"))
      (node (ref "D266") (pin "2") (pinfunction "K_2") (pintype "passive"))
      (node (ref "D270") (pin "2") (pinfunction "K_2") (pintype "passive"))
    )
    (net (code "19") (name "Net-(D201-A)") (class "Default")
      (node (ref "D201") (pin "1") (pinfunction "A_1") (pintype "passive"))
      (node (ref "S201") (pin "1") (pinfunction "1_1") (pintype "passive"))
    )
    (net (code "20") (name "Net-(D202-A)") (class "Default")
      (node (ref "D202") (pin "1") (pinfunction "A_1") (pintype "passive"))
      (node (ref "S202") (pin "1") (pinfunction "1_1") (pintype "passive"))
    )
    (net (code "21") (name "Net-(D203-A)") (class "Default")
      (node (ref "D203") (pin "1") (pinfunction "A_1") (pintype "passive"))
      (node (ref "S203") (pin "1") (pinfunction "1_1") (pintype "passive"))
    )
    (net (code "22") (name "Net-(D204-A)") (class "Default")
      (node (ref "D204") (pin "1") (pinfunction "A_1") (pintype "passive"))
      (node (ref "S204") (pin "1") (pinfunction "1_1") (pintype "passive"))
    )
    (net (code "23") (name "Net-(D205-A)") (class "Default")
      (node (ref "D205") (pin "1") (pinfunction "A_1") (pintype "passive"))
      (node (ref "S205") (pin "1") (pinfunction "1_1") (pintype "passive"))
    )
    (net (code "24") (name "Net-(D206-A)") (class "Default")
      (node (ref "D206") (pin "1") (pinfunction "A_1") (pintype "passive"))
      (node (ref "S206") (pin "1") (pinfunction "1_1") (pintype "passive"))
    )
    (net (code "25") (name "Net-(D207-A)") (class "Default")
      (node (ref "D207") (pin "1") (pinfunction "A_1") (pintype "passive"))
      (node (ref "S207") (pin "1") (pinfunction "1_1") (pintype "passive"))
    )
    (net (code "26") (name "Net-(D208-A)") (class "Default")
      (node (ref "D208") (pin "1") (pinfunction "A_1") (pintype "passive"))
      (node (ref "S208") (pin "1") (pinfunction "1_1") (pintype "passive"))
    )
    (net (code "27") (name "Net-(D209-A)") (class "Default")
      (node (ref "D209") (pin "1") (pinfunction "A_1") (pintype "passive"))
      (node (ref "S209") (pin "1") (pinfunction "1_1") (pintype "passive"))
    )
    (net (code "28") (name "Net-(D210-A)") (class "Default")
      (node (ref "D210") (pin "1") (pinfunction "A_1") (pintype "passive"))
      (node (ref "S210") (pin "1") (pinfunction "1_1") (pintype "passive"))
    )
    (net (code "29") (name "Net-(D211-A)") (class "Default")
      (node (ref "D211") (pin "1") (pinfunction "A_1") (pintype "passive"))
      (node (ref "S211") (pin "1") (pinfunction "1_1") (pintype "passive"))
    )
    (net (code "30") (name "Net-(D212-A)") (class "Default")
      (node (ref "D212") (pin "1") (pinfunction "A_1") (pintype "passive"))
      (node (ref "S212") (pin "1") (pinfunction "1_1") (pintype "passive"))
    )
    (net (code "31") (name "Net-(D213-A)") (class "Default")
      (node (ref "D213") (pin "1") (pinfunction "A_1") (pintype "passive"))
      (node (ref "S213") (pin "1") (pinfunction "1_1") (pintype "passive"))
    )
    (net (code "32") (name "Net-(D214-A)") (class "Default")
      (node (ref "D214") (pin "1") (pinfunction "A_1") (pintype "passive"))
      (node (ref "S214") (pin "1") (pinfunction "1_1") (pintype "passive"))
    )
    (net (code "33") (name "Net-(D215-A)") (class "Default")
      (node (ref "D215") (pin "1") (pinfunction "A_1") (pintype "passive"))
      (node (ref "S215") (pin "1") (pinfunction "1_1") (pintype "passive"))
    )
    (net (code "34") (name "Net-(D216-A)") (class "Default")
      (node (ref "D216") (pin "1") (pinfunction "A_1") (pintype "passive"))
      (node (ref "S216") (pin "1") (pinfunction "1_1") (pintype "passive"))
    )
    (net (code "35") (name "Net-(D217-A)") (class "Default")
      (node (ref "D217") (pin "1") (pinfunction "A_1") (pintype "passive"))
      (node (ref "S217") (pin "1") (pinfunction "1_1") (pintype "passive"))
    )
    (net (code "36") (name "Net-(D218-A)") (class "Default")
      (node (ref "D218") (pin "1") (pinfunction "A_1") (pintype "passive"))
      (node (ref "S218") (pin "1") (pinfunction "1_1") (pintype "passive"))
    )
    (net (code "37") (name "Net-(D219-A)") (class "Default")
      (node (ref "D219") (pin "1") (pinfunction "A_1") (pintype "passive"))
      (node (ref "S219") (pin "1") (pinfunction "1_1") (pintype "passive"))
    )
    (net (code "38") (name "Net-(D220-A)") (class "Default")
      (node (ref "D220") (pin "1") (pinfunction "A_1") (pintype "passive"))
      (node (ref "S220") (pin "1") (pinfunction "1_1") (pintype "passive"))
    )
    (net (code "39") (name "Net-(D221-A)") (class "Default")
      (node (ref "D221") (pin "1") (pinfunction "A_1") (pintype "passive"))
      (node (ref "S221") (pin "1") (pinfunction "1_1") (pintype "passive"))
    )
    (net (code "40") (name "Net-(D222-A)") (class "Default")
      (node (ref "D222") (pin "1") (pinfunction "A_1") (pintype "passive"))
      (node (ref "S222") (pin "1") (pinfunction "1_1") (pintype "passive"))
    )
    (net (code "41") (name "Net-(D223-A)") (class "Default")
      (node (ref "D223") (pin "1") (pinfunction "A_1") (pintype "passive"))
      (node (ref "S223") (pin "1") (pinfunction "1_1") (pintype "passive"))
    )
    (net (code "42") (name "Net-(D224-A)") (class "Default")
      (node (ref "D224") (pin "1") (pinfunction "A_1") (pintype "passive"))
      (node (ref "S224") (pin "1") (pinfunction "1_1") (pintype "passive"))
    )
    (net (code "43") (name "Net-(D225-A)") (class "Default")
      (node (ref "D225") (pin "1") (pinfunction "A_1") (pintype "passive"))
      (node (ref "S225") (pin "1") (pinfunction "1_1") (pintype "passive"))
    )
    (net (code "44") (name "Net-(D226-A)") (class "Default")
      (node (ref "D226") (pin "1") (pinfunction "A_1") (pintype "passive"))
      (node (ref "S226") (pin "1") (pinfunction "1_1") (pintype "passive"))
    )
    (net (code "45") (name "Net-(D227-A)") (class "Default")
      (node (ref "D227") (pin "1") (pinfunction "A_1") (pintype "passive"))
      (node (ref "S227") (pin "1") (pinfunction "1_1") (pintype "passive"))
    )
    (net (code "46") (name "Net-(D228-A)") (class "Default")
      (node (ref "D228") (pin "1") (pinfunction "A_1") (pintype "passive"))
      (node (ref "S228") (pin "2") (pinfunction "2_2") (pintype "passive"))
    )
    (net (code "47") (name "Net-(D229-A)") (class "Default")
      (node (ref "D229") (pin "1") (pinfunction "A_1") (pintype "passive"))
      (node (ref "S229") (pin "1") (pinfunction "1_1") (pintype "passive"))
    )
    (net (code "48") (name "Net-(D230-A)") (class "Default")
      (node (ref "D230") (pin "1") (pinfunction "A_1") (pintype "passive"))
      (node (ref "S230") (pin "1") (pinfunction "1_1") (pintype "passive"))
    )
    (net (code "49") (name "Net-(D231-A)") (class "Default")
      (node (ref "D231") (pin "1") (pinfunction "A_1") (pintype "passive"))
      (node (ref "S231") (pin "1") (pinfunction "1_1") (pintype "passive"))
    )
    (net (code "50") (name "Net-(D232-A)") (class "Default")
      (node (ref "D232") (pin "1") (pinfunction "A_1") (pintype "passive"))
      (node (ref "S232") (pin "1") (pinfunction "1_1") (pintype "passive"))
    )
    (net (code "51") (name "Net-(D233-A)") (class "Default")
      (node (ref "D233") (pin "1") (pinfunction "A_1") (pintype "passive"))
      (node (ref "S233") (pin "1") (pinfunction "1_1") (pintype "passive"))
    )
    (net (code "52") (name "Net-(D234-A)") (class "Default")
      (node (ref "D234") (pin "1") (pinfunction "A_1") (pintype "passive"))
      (node (ref "S234") (pin "1") (pinfunction "1_1") (pintype "passive"))
    )
    (net (code "53") (name "Net-(D235-A)") (class "Default")
      (node (ref "D235") (pin "1") (pinfunction "A_1") (pintype "passive"))
      (node (ref "S235") (pin "1") (pinfunction "1_1") (pintype "passive"))
    )
    (net (code "54") (name "Net-(D236-A)") (class "Default")
      (node (ref "D236") (pin "1") (pinfunction "A_1") (pintype "passive"))
      (node (ref "S236") (pin "1") (pinfunction "1_1") (pintype "passive"))
    )
    (net (code "55") (name "Net-(D237-A)") (class "Default")
      (node (ref "D237") (pin "1") (pinfunction "A_1") (pintype "passive"))
      (node (ref "S237") (pin "1") (pinfunction "1_1") (pintype "passive"))
    )
    (net (code "56") (name "Net-(D238-A)") (class "Default")
      (node (ref "D238") (pin "1") (pinfunction "A_1") (pintype "passive"))
      (node (ref "S238") (pin "1") (pinfunction "1_1") (pintype "passive"))
    )
    (net (code "57") (name "Net-(D239-A)") (class "Default")
      (node (ref "D239") (pin "1") (pinfunction "A_1") (pintype "passive"))
      (node (ref "S239") (pin "1") (pinfunction "1_1") (pintype "passive"))
    )
    (net (code "58") (name "Net-(D240-A)") (class "Default")
      (node (ref "D240") (pin "1") (pinfunction "A_1") (pintype "passive"))
      (node (ref "S240") (pin "1") (pinfunction "1_1") (pintype "passive"))
    )
    (net (code "59") (name "Net-(D241-A)") (class "Default")
      (node (ref "D241") (pin "1") (pinfunction "A_1") (pintype "passive"))
      (node (ref "S241") (pin "1") (pinfunction "1_1") (pintype "passive"))
    )
    (net (code "60") (name "Net-(D242-A)") (class "Default")
      (node (ref "D242") (pin "1") (pinfunction "A_1") (pintype "passive"))
      (node (ref "S242") (pin "1") (pinfunction "1_1") (pintype "passive"))
    )
    (net (code "61") (name "Net-(D243-A)") (class "Default")
      (node (ref "D243") (pin "1") (pinfunction "A_1") (pintype "passive"))
      (node (ref "S243") (pin "1") (pinfunction "1_1") (pintype "passive"))
    )
    (net (code "62") (name "Net-(D244-A)") (class "Default")
      (node (ref "D244") (pin "1") (pinfunction "A_1") (pintype "passive"))
      (node (ref "S244") (pin "1") (pinfunction "1_1") (pintype "passive"))
    )
    (net (code "63") (name "Net-(D245-A)") (class "Default")
      (node (ref "D245") (pin "1") (pinfunction "A_1") (pintype "passive"))
      (node (ref "S245") (pin "1") (pinfunction "1_1") (pintype "passive"))
    )
    (net (code "64") (name "Net-(D246-A)") (class "Default")
      (node (ref "D246") (pin "1") (pinfunction "A_1") (pintype "passive"))
      (node (ref "S246") (pin "1") (pinfunction "1_1") (pintype "passive"))
    )
    (net (code "65") (name "Net-(D247-A)") (class "Default")
      (node (ref "D247") (pin "1") (pinfunction "A_1") (pintype "passive"))
      (node (ref "S247") (pin "1") (pinfunction "1_1") (pintype "passive"))
    )
    (net (code "66") (name "Net-(D248-A)") (class "Default")
      (node (ref "D248") (pin "1") (pinfunction "A_1") (pintype "passive"))
      (node (ref "S248") (pin "1") (pinfunction "1_1") (pintype "passive"))
    )
    (net (code "67") (name "Net-(D249-A)") (class "Default")
      (node (ref "D249") (pin "1") (pinfunction "A_1") (pintype "passive"))
      (node (ref "S249") (pin "1") (pinfunction "1_1") (pintype "passive"))
    )
    (net (code "68") (name "Net-(D250-A)") (class "Default")
      (node (ref "D250") (pin "1") (pinfunction "A_1") (pintype "passive"))
      (node (ref "S250") (pin "1") (pinfunction "1_1") (pintype "passive"))
    )
    (net (code "69") (name "Net-(D251-A)") (class "Default")
      (node (ref "D251") (pin "1") (pinfunction "A_1") (pintype "passive"))
      (node (ref "S251") (pin "1") (pinfunction "1_1") (pintype "passive"))
    )
    (net (code "70") (name "Net-(D252-A)") (class "Default")
      (node (ref "D252") (pin "1") (pinfunction "A_1") (pintype "passive"))
      (node (ref "S252") (pin "1") (pinfunction "1_1") (pintype "passive"))
    )
    (net (code "71") (name "Net-(D253-A)") (class "Default")
      (node (ref "D253") (pin "1") (pinfunction "A_1") (pintype "passive"))
      (node (ref "S253") (pin "1") (pinfunction "1_1") (pintype "passive"))
    )
    (net (code "72") (name "Net-(D254-A)") (class "Default")
      (node (ref "D254") (pin "1") (pinfunction "A_1") (pintype "passive"))
      (node (ref "S254") (pin "1") (pinfunction "1_1") (pintype "passive"))
    )
    (net (code "73") (name "Net-(D255-A)") (class "Default")
      (node (ref "D255") (pin "1") (pinfunction "A_1") (pintype "passive"))
      (node (ref "S255") (pin "1") (pinfunction "1_1") (pintype "passive"))
    )
    (net (code "74") (name "Net-(D256-A)") (class "Default")
      (node (ref "D256") (pin "1") (pinfunction "A_1") (pintype "passive"))
      (node (ref "S256") (pin "1") (pinfunction "1_1") (pintype "passive"))
      (node (ref "S256_1") (pin "1") (pinfunction "1_1") (pintype "passive"))
    )
    (net (code "75") (name "Net-(D257-A)") (class "Default")
      (node (ref "D257") (pin "1") (pinfunction "A_1") (pintype "passive"))
      (node (ref "S257") (pin "1") (pinfunction "1_1") (pintype "passive"))
    )
    (net (code "76") (name "Net-(D258-A)") (class "Default")
      (node (ref "D258") (pin "1") (pinfunction "A_1") (pintype "passive"))
      (node (ref "S258") (pin "1") (pinfunction "1_1") (pintype "passive"))
      (node (ref "S258_1") (pin "1") (pinfunction "1_1") (pintype "passive"))
    )
    (net (code "77") (name "Net-(D259-A)") (class "Default")
      (node (ref "D259") (pin "1") (pinfunction "A_1") (pintype "passive"))
      (node (ref "S259") (pin "1") (pinfunction "1_1") (pintype "passive"))
      (node (ref "S259_1") (pin "1") (pinfunction "1_1") (pintype "passive"))
    )
    (net (code "78") (name "Net-(D260-A)") (class "Default")
      (node (ref "D260") (pin "1") (pinfunction "A_1") (pintype "passive"))
      (node (ref "S260") (pin "1") (pinfunction "1_1") (pintype "passive"))
    )
    (net (code "79") (name "Net-(D261-A)") (class "Default")
      (node (ref "D261") (pin "1") (pinfunction "A_1") (pintype "passive"))
      (node (ref "S261") (pin "2") (pinfunction "2_2") (pintype "passive"))
    )
    (net (code "80") (name "Net-(D262-A)") (class "Default")
      (node (ref "D262") (pin "1") (pinfunction "A_1") (pintype "passive"))
      (node (ref "S262") (pin "1") (pinfunction "1_1") (pintype "passive"))
    )
    (net (code "81") (name "Net-(D263-A)") (class "Default")
      (node (ref "D263") (pin "1") (pinfunction "A_1") (pintype "passive"))
      (node (ref "S263") (pin "1") (pinfunction "1_1") (pintype "passive"))
    )
    (net (code "82") (name "Net-(D264-A)") (class "Default")
      (node (ref "D264") (pin "1") (pinfunction "A_1") (pintype "passive"))
      (node (ref "S264") (pin "2") (pinfunction "2_2") (pintype "passive"))
      (node (ref "S264_1") (pin "1") (pinfunction "1_1") (pintype "passive"))
    )
    (net (code "83") (name "Net-(D265-A)") (class "Default")
      (node (ref "D265") (pin "1") (pinfunction "A_1") (pintype "passive"))
      (node (ref "S265") (pin "1") (pinfunction "1_1") (pintype "passive"))
      (node (ref "S265_1") (pin "1") (pinfunction "1_1") (pintype "passive"))
    )
    (net (code "84") (name "Net-(D266-A)") (class "Default")
      (node (ref "D266") (pin "1") (pinfunction "A_1") (pintype "passive"))
      (node (ref "S266") (pin "1") (pinfunction "1_1") (pintype "passive"))
    )
    (net (code "85") (name "Net-(D267-A)") (class "Default")
      (node (ref "D267") (pin "1") (pinfunction "A_1") (pintype "passive"))
      (node (ref "S267") (pin "1") (pinfunction "1_1") (pintype "passive"))
    )
    (net (code "86") (name "unconnected-(STAB1-Pad1)") (class "Default")
      (node (ref "STAB1") (pin "1") (pinfunction "1_1") (pintype "passive"))
    )
    (net (code "87") (name "unconnected-(STAB2-Pad1)") (class "Default")
      (node (ref "STAB2") (pin "1") (pinfunction "1_1") (pintype "passive"))
    )
  )
)
